# mrShark_14.net
KiCad netlist of a schematic drawn in EAGLE
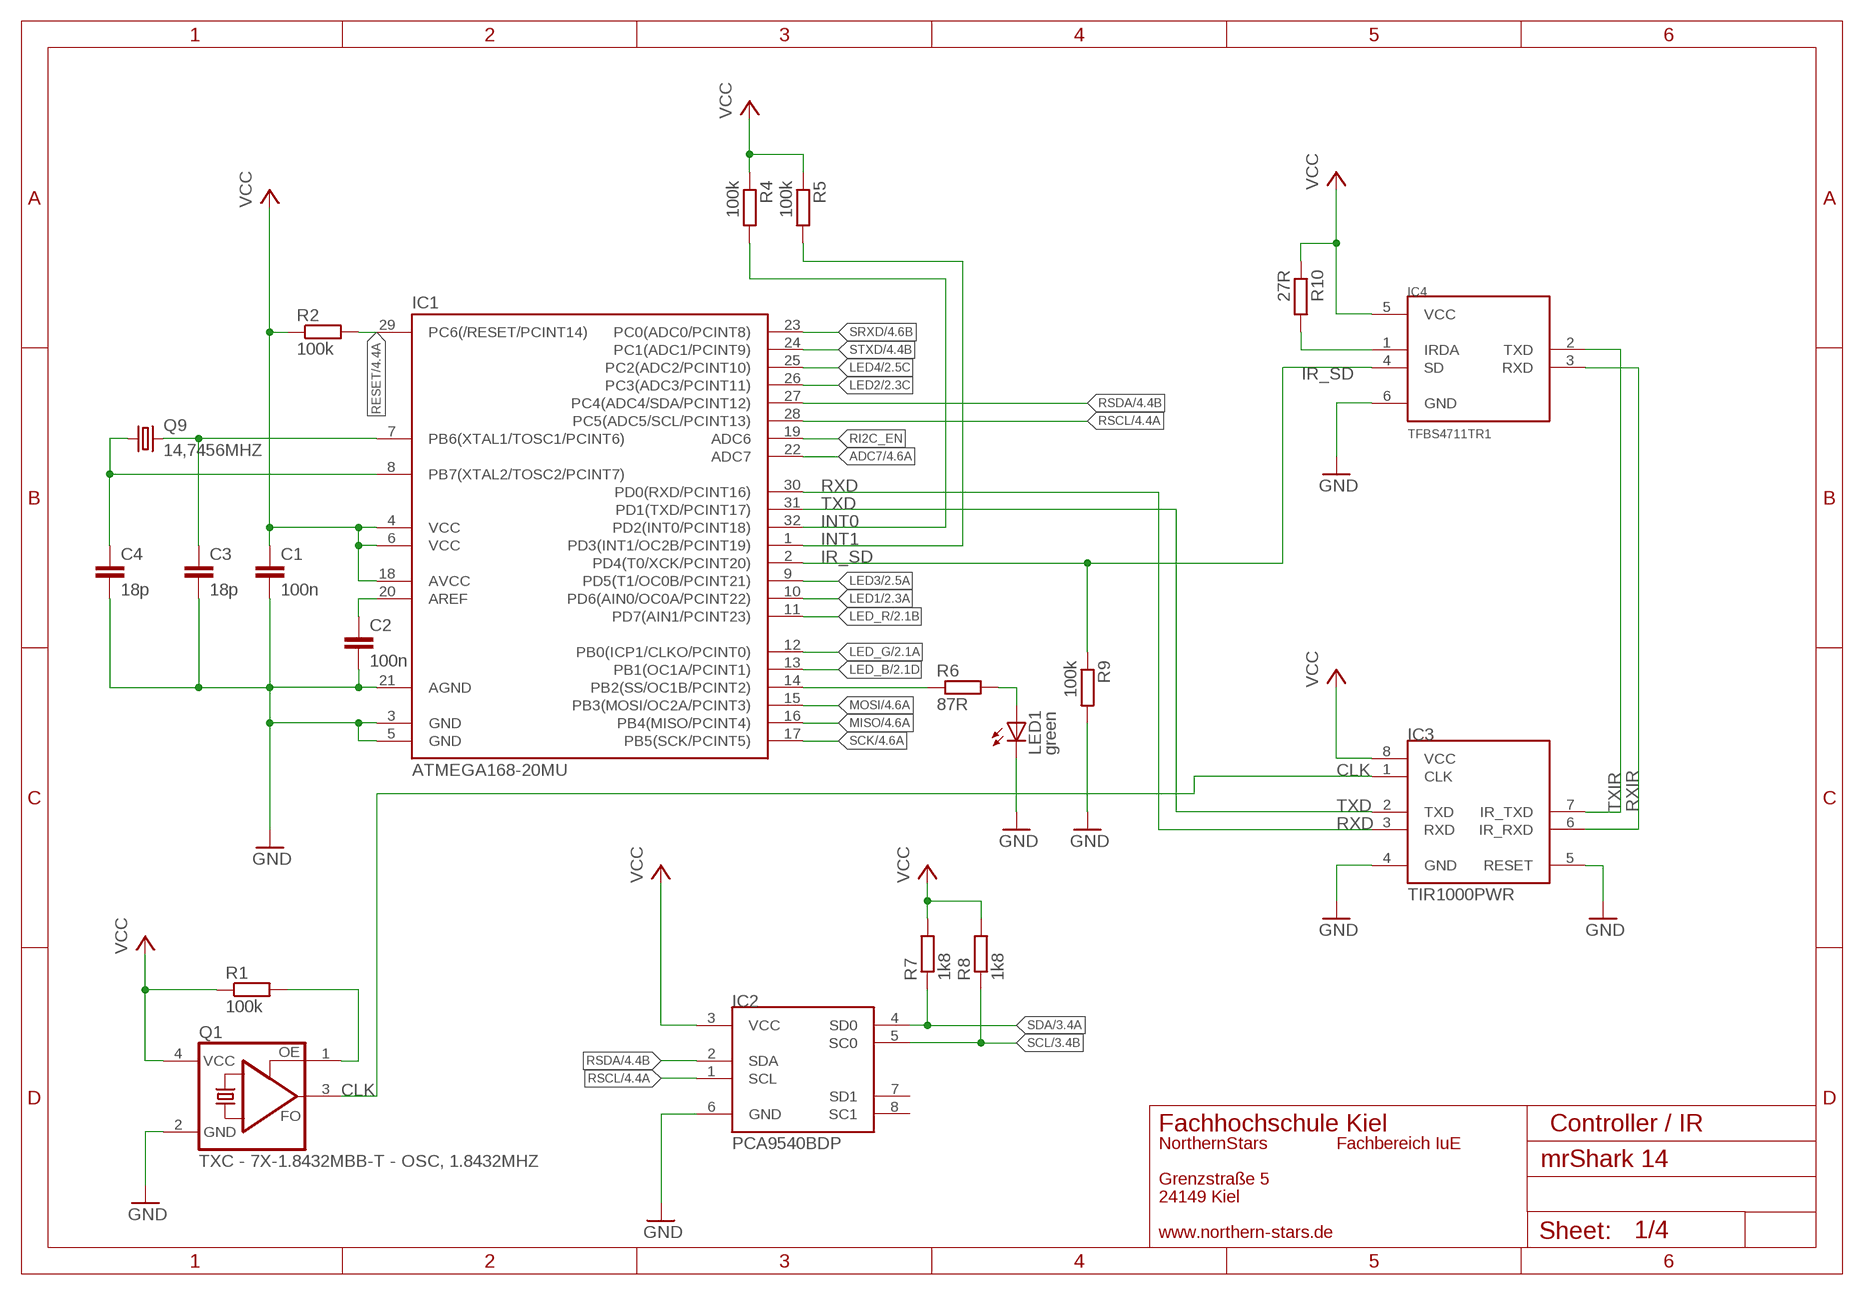
[diagram p0: schematic, sheet 1]
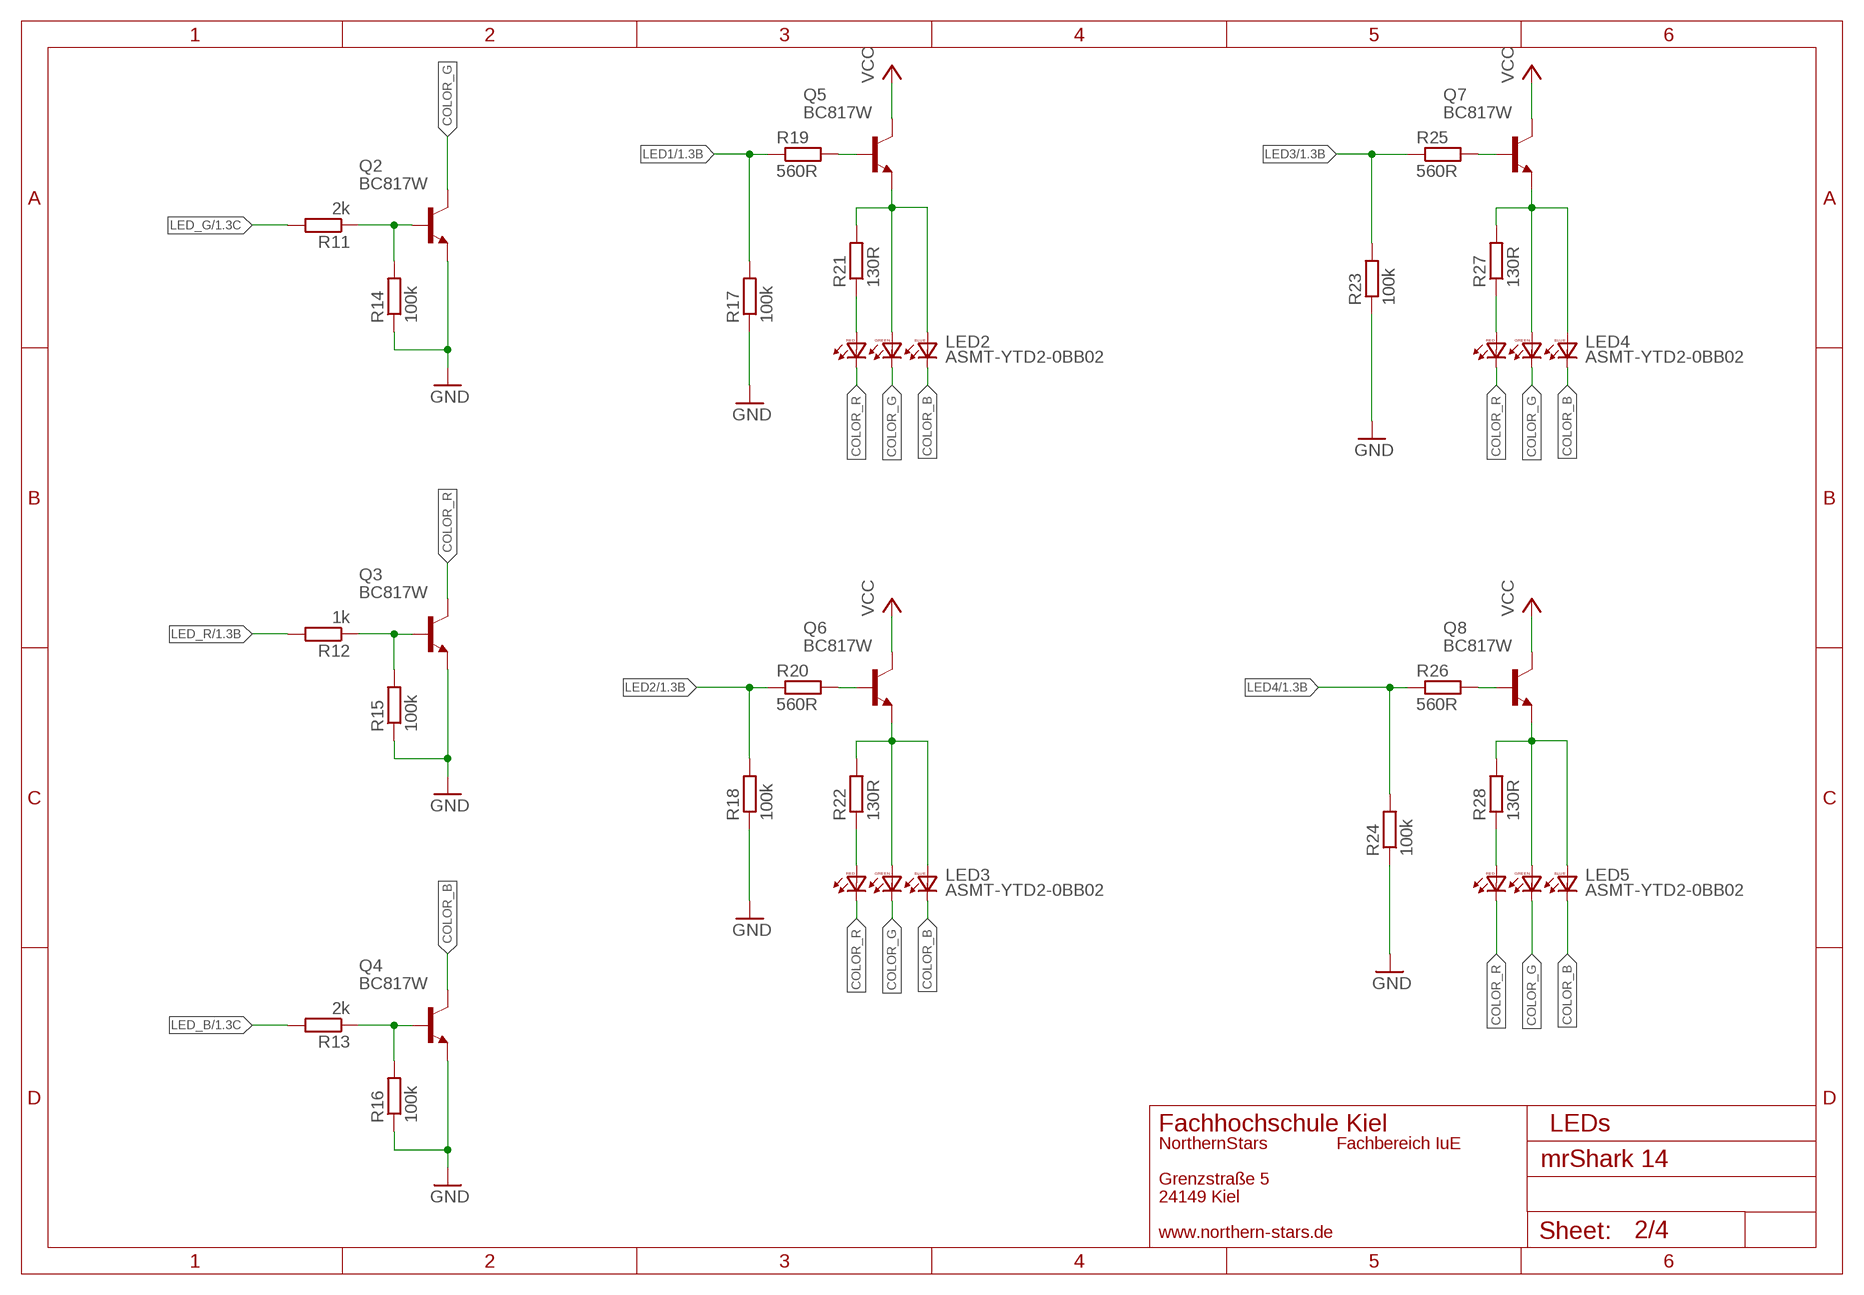
[diagram p1: schematic, sheet 2]
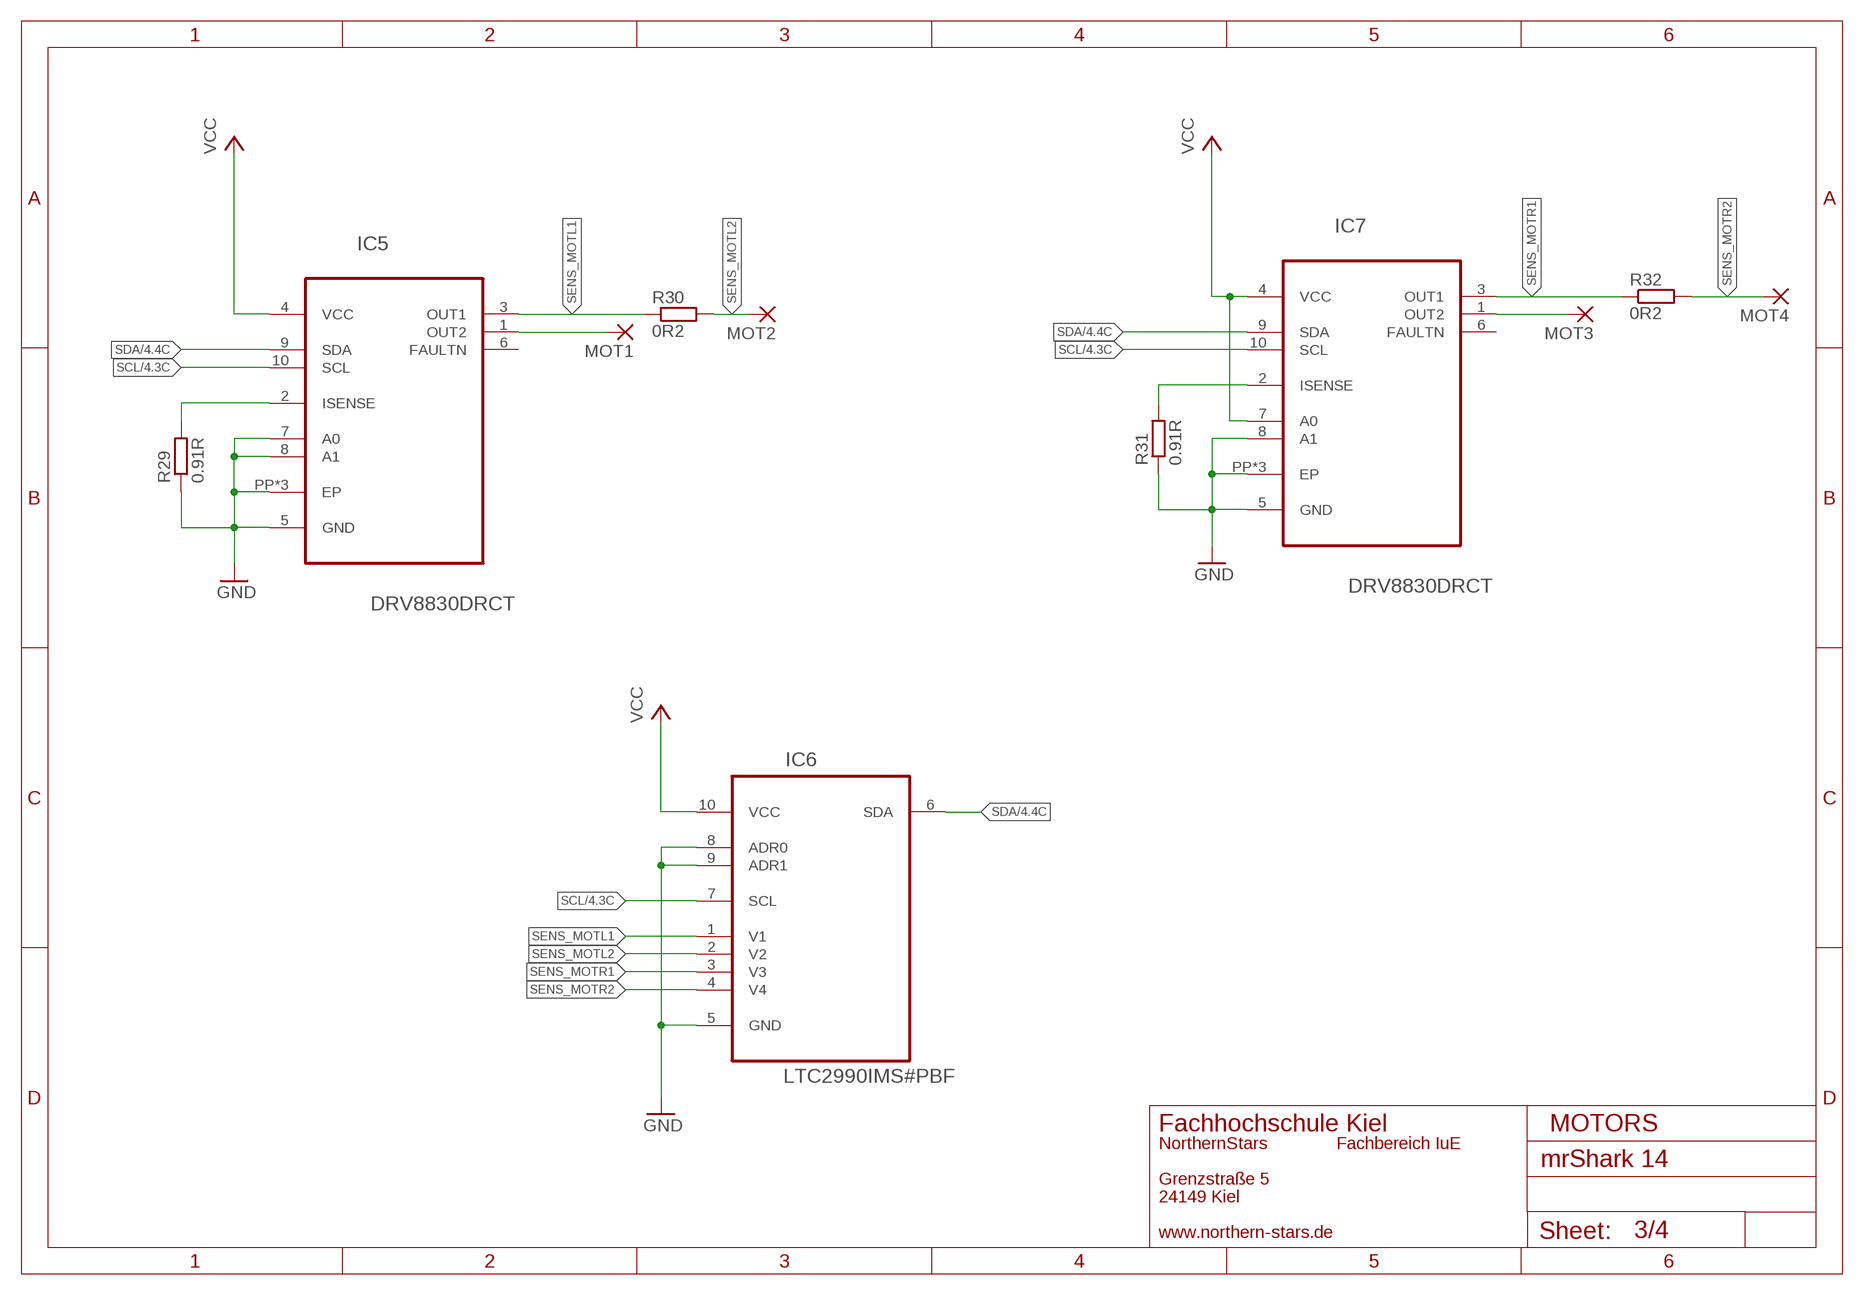
[diagram p2: schematic, sheet 3]
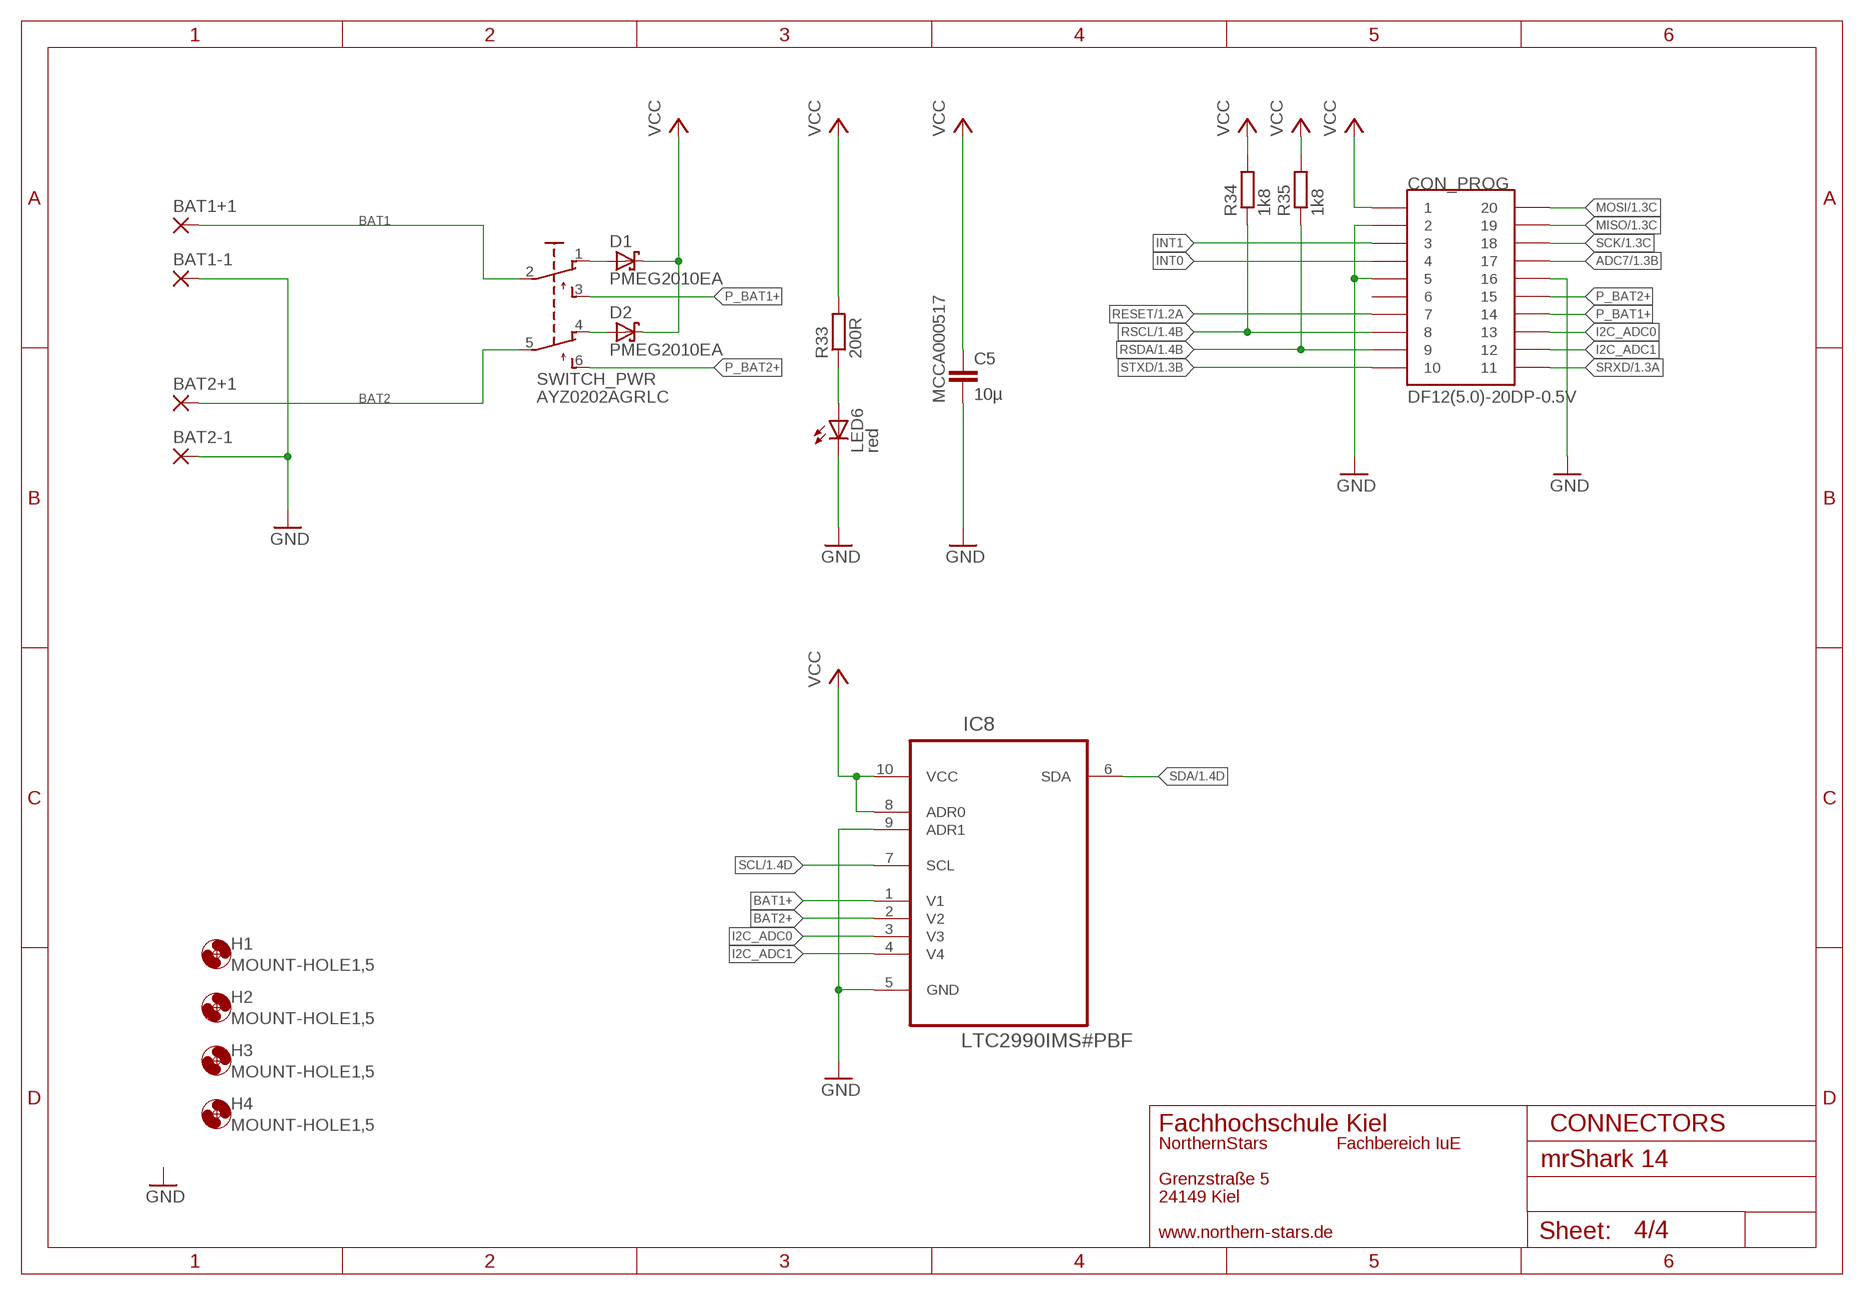
[diagram p3: schematic, sheet 4]

(export (version "E")
  (design (tool "Eeschema 10.0.6"))
  (components
    (comp (ref "BAT1+1")
      (value "1,6/0,9")
      (footprint "eagle-import:1,6_0,9")
      (libsource (lib "eagle-import") (part "1,6/0,9"))
    )
    (comp (ref "BAT1-1")
      (value "1,6/0,9")
      (footprint "eagle-import:1,6_0,9")
      (libsource (lib "eagle-import") (part "1,6/0,9"))
    )
    (comp (ref "BAT2+1")
      (value "1,6/0,9")
      (footprint "eagle-import:1,6_0,9")
      (libsource (lib "eagle-import") (part "1,6/0,9"))
    )
    (comp (ref "BAT2-1")
      (value "1,6/0,9")
      (footprint "eagle-import:1,6_0,9")
      (libsource (lib "eagle-import") (part "1,6/0,9"))
    )
    (comp (ref "C5")
      (value "10µ")
      (footprint "eagle-import:C0603K")
      (libsource (lib "eagle-import") (part "C-EUC0603K"))
    )
    (comp (ref "CON_PROG")
      (value "DF12(5.0)-20DP-0.5V")
      (footprint "eagle-import:DF12-20DP")
      (libsource (lib "eagle-import") (part "DF12-20DP"))
    )
    (comp (ref "D1")
      (value "PMEG2010EA")
      (footprint "eagle-import:SOD323-R")
      (libsource (lib "eagle-import") (part "PMEG2010EAR"))
    )
    (comp (ref "D2")
      (value "PMEG2010EA")
      (footprint "eagle-import:SOD323-R")
      (libsource (lib "eagle-import") (part "PMEG2010EAR"))
    )
    (comp (ref "H1")
      (value "MOUNT-HOLE1,5")
      (footprint "eagle-import:1,5")
      (libsource (lib "eagle-import") (part "MOUNT-HOLE1,5"))
    )
    (comp (ref "H2")
      (value "MOUNT-HOLE1,5")
      (footprint "eagle-import:1,5")
      (libsource (lib "eagle-import") (part "MOUNT-HOLE1,5"))
    )
    (comp (ref "H3")
      (value "MOUNT-HOLE1,5")
      (footprint "eagle-import:1,5")
      (libsource (lib "eagle-import") (part "MOUNT-HOLE1,5"))
    )
    (comp (ref "H4")
      (value "MOUNT-HOLE1,5")
      (footprint "eagle-import:1,5")
      (libsource (lib "eagle-import") (part "MOUNT-HOLE1,5"))
    )
    (comp (ref "IC8")
      (value "LTC2990IMS#PBF")
      (footprint "eagle-import:SOP50P490X110-10N")
      (libsource (lib "eagle-import") (part "LTC2990IMSPBF"))
    )
    (comp (ref "LED6")
      (value "red")
      (footprint "eagle-import:CHIPLED_0603")
      (libsource (lib "eagle-import") (part "LEDCHIPLED_0603"))
    )
    (comp (ref "R33")
      (value "200R")
      (footprint "eagle-import:R0201")
      (libsource (lib "eagle-import") (part "R-EU_R0201"))
    )
    (comp (ref "R34")
      (value "1k8")
      (footprint "eagle-import:R0201")
      (libsource (lib "eagle-import") (part "R-EU_R0201"))
    )
    (comp (ref "R35")
      (value "1k8")
      (footprint "eagle-import:R0201")
      (libsource (lib "eagle-import") (part "R-EU_R0201"))
    )
    (comp (ref "SWITCH_PWR")
      (value "AYZ0202AGRLC")
      (footprint "eagle-import:AYZ0202AGLRC")
      (libsource (lib "eagle-import") (part "AYZ0202AGRLC"))
    )
    (comp (ref "IC5")
      (value "DRV8830DRCT")
      (footprint "eagle-import:S-PDSO-N10")
      (libsource (lib "eagle-import") (part "DRV8830DGQRWSON"))
    )
    (comp (ref "IC6")
      (value "LTC2990IMS#PBF")
      (footprint "eagle-import:SOP50P490X110-10N")
      (libsource (lib "eagle-import") (part "LTC2990IMSPBF"))
    )
    (comp (ref "IC7")
      (value "DRV8830DRCT")
      (footprint "eagle-import:S-PDSO-N10")
      (libsource (lib "eagle-import") (part "DRV8830DGQRWSON"))
    )
    (comp (ref "MOT1")
      (value "1,6/0,9")
      (footprint "eagle-import:1,6_0,9")
      (libsource (lib "eagle-import") (part "1,6/0,9"))
    )
    (comp (ref "MOT2")
      (value "1,6/0,9")
      (footprint "eagle-import:1,6_0,9")
      (libsource (lib "eagle-import") (part "1,6/0,9"))
    )
    (comp (ref "MOT3")
      (value "1,6/0,9")
      (footprint "eagle-import:1,6_0,9")
      (libsource (lib "eagle-import") (part "1,6/0,9"))
    )
    (comp (ref "MOT4")
      (value "1,6/0,9")
      (footprint "eagle-import:1,6_0,9")
      (libsource (lib "eagle-import") (part "1,6/0,9"))
    )
    (comp (ref "R29")
      (value "0.91R")
      (footprint "eagle-import:R0603")
      (libsource (lib "eagle-import") (part "R-EU_R0603"))
    )
    (comp (ref "R30")
      (value "0R2")
      (footprint "eagle-import:R0603")
      (libsource (lib "eagle-import") (part "R-EU_R0603"))
    )
    (comp (ref "R31")
      (value "0.91R")
      (footprint "eagle-import:R0603")
      (libsource (lib "eagle-import") (part "R-EU_R0603"))
    )
    (comp (ref "R32")
      (value "0R2")
      (footprint "eagle-import:R0603")
      (libsource (lib "eagle-import") (part "R-EU_R0603"))
    )
    (comp (ref "LED2")
      (value "ASMT-YTD2-0BB02")
      (footprint "eagle-import:PLCC6K")
      (libsource (lib "eagle-import") (part "PLCC6K"))
    )
    (comp (ref "LED3")
      (value "ASMT-YTD2-0BB02")
      (footprint "eagle-import:PLCC6K")
      (libsource (lib "eagle-import") (part "PLCC6K"))
    )
    (comp (ref "LED4")
      (value "ASMT-YTD2-0BB02")
      (footprint "eagle-import:PLCC6K")
      (libsource (lib "eagle-import") (part "PLCC6K"))
    )
    (comp (ref "LED5")
      (value "ASMT-YTD2-0BB02")
      (footprint "eagle-import:PLCC6K")
      (libsource (lib "eagle-import") (part "PLCC6K"))
    )
    (comp (ref "Q2")
      (value "BC817W")
      (footprint "eagle-import:SOT323-BEC")
      (libsource (lib "eagle-import") (part "BC817W"))
    )
    (comp (ref "Q3")
      (value "BC817W")
      (footprint "eagle-import:SOT323-BEC")
      (libsource (lib "eagle-import") (part "BC817W"))
    )
    (comp (ref "Q4")
      (value "BC817W")
      (footprint "eagle-import:SOT323-BEC")
      (libsource (lib "eagle-import") (part "BC817W"))
    )
    (comp (ref "Q5")
      (value "BC817W")
      (footprint "eagle-import:SOT323-BEC")
      (libsource (lib "eagle-import") (part "BC817W"))
    )
    (comp (ref "Q6")
      (value "BC817W")
      (footprint "eagle-import:SOT323-BEC")
      (libsource (lib "eagle-import") (part "BC817W"))
    )
    (comp (ref "Q7")
      (value "BC817W")
      (footprint "eagle-import:SOT323-BEC")
      (libsource (lib "eagle-import") (part "BC817W"))
    )
    (comp (ref "Q8")
      (value "BC817W")
      (footprint "eagle-import:SOT323-BEC")
      (libsource (lib "eagle-import") (part "BC817W"))
    )
    (comp (ref "R11")
      (value "2k")
      (footprint "eagle-import:R0201")
      (libsource (lib "eagle-import") (part "R-EU_R0201"))
    )
    (comp (ref "R12")
      (value "1k")
      (footprint "eagle-import:R0201")
      (libsource (lib "eagle-import") (part "R-EU_R0201"))
    )
    (comp (ref "R13")
      (value "2k")
      (footprint "eagle-import:R0201")
      (libsource (lib "eagle-import") (part "R-EU_R0201"))
    )
    (comp (ref "R14")
      (value "100k")
      (footprint "eagle-import:R0201")
      (libsource (lib "eagle-import") (part "R-EU_R0201"))
    )
    (comp (ref "R15")
      (value "100k")
      (footprint "eagle-import:R0201")
      (libsource (lib "eagle-import") (part "R-EU_R0201"))
    )
    (comp (ref "R16")
      (value "100k")
      (footprint "eagle-import:R0201")
      (libsource (lib "eagle-import") (part "R-EU_R0201"))
    )
    (comp (ref "R17")
      (value "100k")
      (footprint "eagle-import:R0201")
      (libsource (lib "eagle-import") (part "R-EU_R0201"))
    )
    (comp (ref "R18")
      (value "100k")
      (footprint "eagle-import:R0201")
      (libsource (lib "eagle-import") (part "R-EU_R0201"))
    )
    (comp (ref "R19")
      (value "560R")
      (footprint "eagle-import:R0201")
      (libsource (lib "eagle-import") (part "R-EU_R0201"))
    )
    (comp (ref "R20")
      (value "560R")
      (footprint "eagle-import:R0201")
      (libsource (lib "eagle-import") (part "R-EU_R0201"))
    )
    (comp (ref "R21")
      (value "130R")
      (footprint "eagle-import:R0201")
      (libsource (lib "eagle-import") (part "R-EU_R0201"))
    )
    (comp (ref "R22")
      (value "130R")
      (footprint "eagle-import:R0201")
      (libsource (lib "eagle-import") (part "R-EU_R0201"))
    )
    (comp (ref "R23")
      (value "100k")
      (footprint "eagle-import:R0201")
      (libsource (lib "eagle-import") (part "R-EU_R0201"))
    )
    (comp (ref "R24")
      (value "100k")
      (footprint "eagle-import:R0201")
      (libsource (lib "eagle-import") (part "R-EU_R0201"))
    )
    (comp (ref "R25")
      (value "560R")
      (footprint "eagle-import:R0201")
      (libsource (lib "eagle-import") (part "R-EU_R0201"))
    )
    (comp (ref "R26")
      (value "560R")
      (footprint "eagle-import:R0201")
      (libsource (lib "eagle-import") (part "R-EU_R0201"))
    )
    (comp (ref "R27")
      (value "130R")
      (footprint "eagle-import:R0201")
      (libsource (lib "eagle-import") (part "R-EU_R0201"))
    )
    (comp (ref "R28")
      (value "130R")
      (footprint "eagle-import:R0201")
      (libsource (lib "eagle-import") (part "R-EU_R0201"))
    )
    (comp (ref "C1")
      (value "100n")
      (footprint "eagle-import:C0201")
      (libsource (lib "eagle-import") (part "C-EUC0201"))
    )
    (comp (ref "C2")
      (value "100n")
      (footprint "eagle-import:C0201")
      (libsource (lib "eagle-import") (part "C-EUC0201"))
    )
    (comp (ref "C3")
      (value "18p")
      (footprint "eagle-import:C0201")
      (libsource (lib "eagle-import") (part "C-EUC0201"))
    )
    (comp (ref "C4")
      (value "18p")
      (footprint "eagle-import:C0201")
      (libsource (lib "eagle-import") (part "C-EUC0201"))
    )
    (comp (ref "IC1")
      (value "ATMEGA168-20MU")
      (footprint "eagle-import:MLF32")
      (libsource (lib "eagle-import") (part "ATMEGA48/88/168-MU"))
    )
    (comp (ref "IC2")
      (value "PCA9540BDP")
      (footprint "eagle-import:TSSOP8")
      (libsource (lib "eagle-import") (part "PCA9540TSSOP8"))
    )
    (comp (ref "IC3")
      (value "TIR1000PWR")
      (footprint "eagle-import:PW_R-PDSO-G08")
      (libsource (lib "eagle-import") (part "TIR1000PWR"))
    )
    (comp (ref "IC4")
      (value "TFBS4711TR1")
      (footprint "eagle-import:TFBS4711")
      (libsource (lib "eagle-import") (part "TFBS4711TR1"))
    )
    (comp (ref "LED1")
      (value "green")
      (footprint "eagle-import:CHIPLED_0603")
      (libsource (lib "eagle-import") (part "LEDCHIPLED_0603"))
    )
    (comp (ref "Q1")
      (value "TXC - 7X-1.8432MBB-T - OSC, 1.8432MHZ")
      (footprint "eagle-import:3.2X2.5")
      (libsource (lib "eagle-import") (part "7X-SERIES"))
    )
    (comp (ref "Q9")
      (value "14,7456MHZ")
      (footprint "eagle-import:TXC_7B_SERIES")
      (libsource (lib "eagle-import") (part "TXC-7B-SERIESSMD"))
    )
    (comp (ref "R1")
      (value "100k")
      (footprint "eagle-import:R0201")
      (libsource (lib "eagle-import") (part "R-EU_R0201"))
    )
    (comp (ref "R2")
      (value "100k")
      (footprint "eagle-import:R0201")
      (libsource (lib "eagle-import") (part "R-EU_R0201"))
    )
    (comp (ref "R4")
      (value "100k")
      (footprint "eagle-import:R0201")
      (libsource (lib "eagle-import") (part "R-EU_R0201"))
    )
    (comp (ref "R5")
      (value "100k")
      (footprint "eagle-import:R0201")
      (libsource (lib "eagle-import") (part "R-EU_R0201"))
    )
    (comp (ref "R6")
      (value "87R")
      (footprint "eagle-import:R0201")
      (libsource (lib "eagle-import") (part "R-EU_R0201"))
    )
    (comp (ref "R7")
      (value "1k8")
      (footprint "eagle-import:R0201")
      (libsource (lib "eagle-import") (part "R-EU_R0201"))
    )
    (comp (ref "R8")
      (value "1k8")
      (footprint "eagle-import:R0201")
      (libsource (lib "eagle-import") (part "R-EU_R0201"))
    )
    (comp (ref "R9")
      (value "100k")
      (footprint "eagle-import:R0201")
      (libsource (lib "eagle-import") (part "R-EU_R0201"))
    )
    (comp (ref "R10")
      (value "27R")
      (footprint "eagle-import:R0201")
      (libsource (lib "eagle-import") (part "R-EU_R0201"))
    )
  )
  (nets
    (net (code "1") (name "ADC7") (class "Default")
      (node (ref "CON_PROG") (pin "17") (pinfunction "17_17") (pintype "bidirectional"))
      (node (ref "IC1") (pin "22") (pinfunction "ADC7_22") (pintype "passive"))
    )
    (net (code "2") (name "BAT1") (class "Default")
      (node (ref "BAT1+1") (pin "1") (pinfunction "P_1") (pintype "passive"))
      (node (ref "SWITCH_PWR") (pin "2") (pinfunction "P_2") (pintype "passive"))
    )
    (net (code "3") (name "BAT1+") (class "Default")
      (node (ref "D1") (pin "A") (pinfunction "A_A") (pintype "passive"))
      (node (ref "IC8") (pin "1") (pinfunction "V1_1") (pintype "input"))
      (node (ref "SWITCH_PWR") (pin "1") (pinfunction "O_1") (pintype "passive"))
    )
    (net (code "4") (name "BAT2") (class "Default")
      (node (ref "BAT2+1") (pin "1") (pinfunction "P_1") (pintype "passive"))
      (node (ref "SWITCH_PWR") (pin "5") (pinfunction "P1_5") (pintype "passive"))
    )
    (net (code "5") (name "BAT2+") (class "Default")
      (node (ref "D2") (pin "A") (pinfunction "A_A") (pintype "passive"))
      (node (ref "IC8") (pin "2") (pinfunction "V2_2") (pintype "input"))
      (node (ref "SWITCH_PWR") (pin "4") (pinfunction "O1_4") (pintype "passive"))
    )
    (net (code "6") (name "CLK") (class "Default")
      (node (ref "IC3") (pin "1") (pinfunction "CLK_1") (pintype "bidirectional"))
      (node (ref "Q1") (pin "3") (pinfunction "FO_3") (pintype "output"))
    )
    (net (code "7") (name "COLOR_B") (class "Default")
      (node (ref "LED2") (pin "1") (pinfunction "BC_1") (pintype "passive"))
      (node (ref "LED3") (pin "1") (pinfunction "BC_1") (pintype "passive"))
      (node (ref "LED4") (pin "1") (pinfunction "BC_1") (pintype "passive"))
      (node (ref "LED5") (pin "1") (pinfunction "BC_1") (pintype "passive"))
      (node (ref "Q4") (pin "C") (pinfunction "C_C") (pintype "passive"))
    )
    (net (code "8") (name "COLOR_G") (class "Default")
      (node (ref "LED2") (pin "2") (pinfunction "GC_2") (pintype "passive"))
      (node (ref "LED3") (pin "2") (pinfunction "GC_2") (pintype "passive"))
      (node (ref "LED4") (pin "2") (pinfunction "GC_2") (pintype "passive"))
      (node (ref "LED5") (pin "2") (pinfunction "GC_2") (pintype "passive"))
      (node (ref "Q2") (pin "C") (pinfunction "C_C") (pintype "passive"))
    )
    (net (code "9") (name "COLOR_R") (class "Default")
      (node (ref "LED2") (pin "3") (pinfunction "RC_3") (pintype "passive"))
      (node (ref "LED3") (pin "3") (pinfunction "RC_3") (pintype "passive"))
      (node (ref "LED4") (pin "3") (pinfunction "RC_3") (pintype "passive"))
      (node (ref "LED5") (pin "3") (pinfunction "RC_3") (pintype "passive"))
      (node (ref "Q3") (pin "C") (pinfunction "C_C") (pintype "passive"))
    )
    (net (code "10") (name "GND") (class "Default")
      (node (ref "BAT1-1") (pin "1") (pinfunction "P_1") (pintype "passive"))
      (node (ref "BAT2-1") (pin "1") (pinfunction "P_1") (pintype "passive"))
      (node (ref "C1") (pin "2") (pinfunction "2_2") (pintype "passive"))
      (node (ref "C2") (pin "2") (pinfunction "2_2") (pintype "passive"))
      (node (ref "C3") (pin "2") (pinfunction "2_2") (pintype "passive"))
      (node (ref "C4") (pin "2") (pinfunction "2_2") (pintype "passive"))
      (node (ref "C5") (pin "2") (pinfunction "2_2") (pintype "passive"))
      (node (ref "CON_PROG") (pin "16") (pinfunction "16_16") (pintype "bidirectional"))
      (node (ref "CON_PROG") (pin "2") (pinfunction "2_2") (pintype "bidirectional"))
      (node (ref "CON_PROG") (pin "5") (pinfunction "5_5") (pintype "bidirectional"))
      (node (ref "IC1") (pin "21") (pinfunction "AGND_21") (pintype "power_in"))
      (node (ref "IC1") (pin "3") (pinfunction "GND_3") (pintype "power_in"))
      (node (ref "IC1") (pin "5") (pinfunction "GND_5") (pintype "power_in"))
      (node (ref "IC2") (pin "6") (pinfunction "GND_6") (pintype "bidirectional"))
      (node (ref "IC3") (pin "4") (pinfunction "GND_4") (pintype "bidirectional"))
      (node (ref "IC3") (pin "5") (pinfunction "RESET_5") (pintype "bidirectional"))
      (node (ref "IC4") (pin "6") (pinfunction "GND_6") (pintype "bidirectional"))
      (node (ref "IC5") (pin "5") (pinfunction "GND_5") (pintype "passive"))
      (node (ref "IC5") (pin "7") (pinfunction "A0_7") (pintype "input"))
      (node (ref "IC5") (pin "8") (pinfunction "A1_8") (pintype "input"))
      (node (ref "IC5") (pin "PP") (pinfunction "EP_PP") (pintype "passive"))
      (node (ref "IC5") (pin "PP@1") (pinfunction "EP_PP@1") (pintype "passive"))
      (node (ref "IC5") (pin "PP@2") (pinfunction "EP_PP@2") (pintype "passive"))
      (node (ref "IC6") (pin "5") (pinfunction "GND_5") (pintype "passive"))
      (node (ref "IC6") (pin "8") (pinfunction "ADR0_8") (pintype "input"))
      (node (ref "IC6") (pin "9") (pinfunction "ADR1_9") (pintype "input"))
      (node (ref "IC7") (pin "5") (pinfunction "GND_5") (pintype "passive"))
      (node (ref "IC7") (pin "8") (pinfunction "A1_8") (pintype "input"))
      (node (ref "IC7") (pin "PP") (pinfunction "EP_PP") (pintype "passive"))
      (node (ref "IC7") (pin "PP@1") (pinfunction "EP_PP@1") (pintype "passive"))
      (node (ref "IC7") (pin "PP@2") (pinfunction "EP_PP@2") (pintype "passive"))
      (node (ref "IC8") (pin "5") (pinfunction "GND_5") (pintype "passive"))
      (node (ref "IC8") (pin "9") (pinfunction "ADR1_9") (pintype "input"))
      (node (ref "LED1") (pin "C") (pinfunction "C_C") (pintype "passive"))
      (node (ref "LED6") (pin "C") (pinfunction "C_C") (pintype "passive"))
      (node (ref "Q1") (pin "2") (pinfunction "GND_2") (pintype "power_in"))
      (node (ref "Q2") (pin "E") (pinfunction "E_E") (pintype "passive"))
      (node (ref "Q3") (pin "E") (pinfunction "E_E") (pintype "passive"))
      (node (ref "Q4") (pin "E") (pinfunction "E_E") (pintype "passive"))
      (node (ref "R14") (pin "1") (pinfunction "1_1") (pintype "passive"))
      (node (ref "R15") (pin "1") (pinfunction "1_1") (pintype "passive"))
      (node (ref "R16") (pin "1") (pinfunction "1_1") (pintype "passive"))
      (node (ref "R17") (pin "1") (pinfunction "1_1") (pintype "passive"))
      (node (ref "R18") (pin "1") (pinfunction "1_1") (pintype "passive"))
      (node (ref "R23") (pin "1") (pinfunction "1_1") (pintype "passive"))
      (node (ref "R24") (pin "1") (pinfunction "1_1") (pintype "passive"))
      (node (ref "R29") (pin "1") (pinfunction "1_1") (pintype "passive"))
      (node (ref "R31") (pin "1") (pinfunction "1_1") (pintype "passive"))
      (node (ref "R9") (pin "2") (pinfunction "2_2") (pintype "passive"))
    )
    (net (code "11") (name "I2C_ADC0") (class "Default")
      (node (ref "CON_PROG") (pin "13") (pinfunction "13_13") (pintype "bidirectional"))
      (node (ref "IC8") (pin "3") (pinfunction "V3_3") (pintype "input"))
    )
    (net (code "12") (name "I2C_ADC1") (class "Default")
      (node (ref "CON_PROG") (pin "12") (pinfunction "12_12") (pintype "bidirectional"))
      (node (ref "IC8") (pin "4") (pinfunction "V4_4") (pintype "input"))
    )
    (net (code "13") (name "INT0") (class "Default")
      (node (ref "CON_PROG") (pin "4") (pinfunction "4_4") (pintype "bidirectional"))
      (node (ref "IC1") (pin "32") (pinfunction "PD2(INT0/PCINT18)_32") (pintype "bidirectional"))
      (node (ref "R4") (pin "2") (pinfunction "2_2") (pintype "passive"))
    )
    (net (code "14") (name "INT1") (class "Default")
      (node (ref "CON_PROG") (pin "3") (pinfunction "3_3") (pintype "bidirectional"))
      (node (ref "IC1") (pin "1") (pinfunction "PD3(INT1/OC2B/PCINT19)_1") (pintype "bidirectional"))
      (node (ref "R5") (pin "2") (pinfunction "2_2") (pintype "passive"))
    )
    (net (code "15") (name "IR_SD") (class "Default")
      (node (ref "IC1") (pin "2") (pinfunction "PD4(T0/XCK/PCINT20)_2") (pintype "bidirectional"))
      (node (ref "IC4") (pin "4") (pinfunction "SD_4") (pintype "bidirectional"))
      (node (ref "R9") (pin "1") (pinfunction "1_1") (pintype "passive"))
    )
    (net (code "16") (name "LED1") (class "Default")
      (node (ref "IC1") (pin "10") (pinfunction "PD6(AIN0/OC0A/PCINT22)_10") (pintype "bidirectional"))
      (node (ref "R17") (pin "2") (pinfunction "2_2") (pintype "passive"))
      (node (ref "R19") (pin "1") (pinfunction "1_1") (pintype "passive"))
    )
    (net (code "17") (name "LED2") (class "Default")
      (node (ref "IC1") (pin "26") (pinfunction "PC3(ADC3/PCINT11)_26") (pintype "bidirectional"))
      (node (ref "R18") (pin "2") (pinfunction "2_2") (pintype "passive"))
      (node (ref "R20") (pin "1") (pinfunction "1_1") (pintype "passive"))
    )
    (net (code "18") (name "LED3") (class "Default")
      (node (ref "IC1") (pin "9") (pinfunction "PD5(T1/OC0B/PCINT21)_9") (pintype "bidirectional"))
      (node (ref "R23") (pin "2") (pinfunction "2_2") (pintype "passive"))
      (node (ref "R25") (pin "1") (pinfunction "1_1") (pintype "passive"))
    )
    (net (code "19") (name "LED4") (class "Default")
      (node (ref "IC1") (pin "25") (pinfunction "PC2(ADC2/PCINT10)_25") (pintype "bidirectional"))
      (node (ref "R24") (pin "2") (pinfunction "2_2") (pintype "passive"))
      (node (ref "R26") (pin "1") (pinfunction "1_1") (pintype "passive"))
    )
    (net (code "20") (name "LED_B") (class "Default")
      (node (ref "IC1") (pin "13") (pinfunction "PB1(OC1A/PCINT1)_13") (pintype "bidirectional"))
      (node (ref "R13") (pin "2") (pinfunction "2_2") (pintype "passive"))
    )
    (net (code "21") (name "LED_G") (class "Default")
      (node (ref "IC1") (pin "12") (pinfunction "PB0(ICP1/CLKO/PCINT0)_12") (pintype "bidirectional"))
      (node (ref "R11") (pin "2") (pinfunction "2_2") (pintype "passive"))
    )
    (net (code "22") (name "LED_R") (class "Default")
      (node (ref "IC1") (pin "11") (pinfunction "PD7(AIN1/PCINT23)_11") (pintype "bidirectional"))
      (node (ref "R12") (pin "2") (pinfunction "2_2") (pintype "passive"))
    )
    (net (code "23") (name "MISO") (class "Default")
      (node (ref "CON_PROG") (pin "19") (pinfunction "19_19") (pintype "bidirectional"))
      (node (ref "IC1") (pin "16") (pinfunction "PB4(MISO/PCINT4)_16") (pintype "bidirectional"))
    )
    (net (code "24") (name "MOSI") (class "Default")
      (node (ref "CON_PROG") (pin "20") (pinfunction "20_20") (pintype "bidirectional"))
      (node (ref "IC1") (pin "15") (pinfunction "PB3(MOSI/OC2A/PCINT3)_15") (pintype "bidirectional"))
    )
    (net (code "25") (name "Net-(IC1-AREF)") (class "Default")
      (node (ref "C2") (pin "1") (pinfunction "1_1") (pintype "passive"))
      (node (ref "IC1") (pin "20") (pinfunction "AREF_20") (pintype "passive"))
    )
    (net (code "26") (name "Net-(IC1-PB2(SS{slash}OC1B{slash}PCINT2))") (class "Default")
      (node (ref "IC1") (pin "14") (pinfunction "PB2(SS/OC1B/PCINT2)_14") (pintype "bidirectional"))
      (node (ref "R6") (pin "1") (pinfunction "1_1") (pintype "passive"))
    )
    (net (code "27") (name "Net-(IC1-PB6(XTAL1{slash}TOSC1{slash}PCINT6))") (class "Default")
      (node (ref "C3") (pin "1") (pinfunction "1_1") (pintype "passive"))
      (node (ref "IC1") (pin "7") (pinfunction "PB6(XTAL1/TOSC1/PCINT6)_7") (pintype "bidirectional"))
      (node (ref "Q9") (pin "3") (pinfunction "2_3") (pintype "passive"))
    )
    (net (code "28") (name "Net-(IC1-PB7(XTAL2{slash}TOSC2{slash}PCINT7))") (class "Default")
      (node (ref "C4") (pin "1") (pinfunction "1_1") (pintype "passive"))
      (node (ref "IC1") (pin "8") (pinfunction "PB7(XTAL2/TOSC2/PCINT7)_8") (pintype "bidirectional"))
      (node (ref "Q9") (pin "1") (pinfunction "1_1") (pintype "passive"))
    )
    (net (code "29") (name "Net-(IC4-IRDA)") (class "Default")
      (node (ref "IC4") (pin "1") (pinfunction "IRDA_1") (pintype "bidirectional"))
      (node (ref "R10") (pin "2") (pinfunction "2_2") (pintype "passive"))
    )
    (net (code "30") (name "Net-(IC5-ISENSE)") (class "Default")
      (node (ref "IC5") (pin "2") (pinfunction "ISENSE_2") (pintype "input"))
      (node (ref "R29") (pin "2") (pinfunction "2_2") (pintype "passive"))
    )
    (net (code "31") (name "Net-(IC5-OUT2)") (class "Default")
      (node (ref "IC5") (pin "1") (pinfunction "OUT2_1") (pintype "output"))
      (node (ref "MOT1") (pin "1") (pinfunction "P_1") (pintype "passive"))
    )
    (net (code "32") (name "Net-(IC7-ISENSE)") (class "Default")
      (node (ref "IC7") (pin "2") (pinfunction "ISENSE_2") (pintype "input"))
      (node (ref "R31") (pin "2") (pinfunction "2_2") (pintype "passive"))
    )
    (net (code "33") (name "Net-(IC7-OUT2)") (class "Default")
      (node (ref "IC7") (pin "1") (pinfunction "OUT2_1") (pintype "output"))
      (node (ref "MOT3") (pin "1") (pinfunction "P_1") (pintype "passive"))
    )
    (net (code "34") (name "Net-(LED1-PadA)") (class "Default")
      (node (ref "LED1") (pin "A") (pinfunction "A_A") (pintype "passive"))
      (node (ref "R6") (pin "2") (pinfunction "2_2") (pintype "passive"))
    )
    (net (code "35") (name "Net-(LED2-BA)") (class "Default")
      (node (ref "LED2") (pin "5") (pinfunction "GA_5") (pintype "passive"))
      (node (ref "LED2") (pin "6") (pinfunction "BA_6") (pintype "passive"))
      (node (ref "Q5") (pin "E") (pinfunction "E_E") (pintype "passive"))
      (node (ref "R21") (pin "2") (pinfunction "2_2") (pintype "passive"))
    )
    (net (code "36") (name "Net-(LED2-RA)") (class "Default")
      (node (ref "LED2") (pin "4") (pinfunction "RA_4") (pintype "passive"))
      (node (ref "R21") (pin "1") (pinfunction "1_1") (pintype "passive"))
    )
    (net (code "37") (name "Net-(LED3-BA)") (class "Default")
      (node (ref "LED3") (pin "5") (pinfunction "GA_5") (pintype "passive"))
      (node (ref "LED3") (pin "6") (pinfunction "BA_6") (pintype "passive"))
      (node (ref "Q6") (pin "E") (pinfunction "E_E") (pintype "passive"))
      (node (ref "R22") (pin "2") (pinfunction "2_2") (pintype "passive"))
    )
    (net (code "38") (name "Net-(LED3-RA)") (class "Default")
      (node (ref "LED3") (pin "4") (pinfunction "RA_4") (pintype "passive"))
      (node (ref "R22") (pin "1") (pinfunction "1_1") (pintype "passive"))
    )
    (net (code "39") (name "Net-(LED4-BA)") (class "Default")
      (node (ref "LED4") (pin "5") (pinfunction "GA_5") (pintype "passive"))
      (node (ref "LED4") (pin "6") (pinfunction "BA_6") (pintype "passive"))
      (node (ref "Q7") (pin "E") (pinfunction "E_E") (pintype "passive"))
      (node (ref "R27") (pin "2") (pinfunction "2_2") (pintype "passive"))
    )
    (net (code "40") (name "Net-(LED4-RA)") (class "Default")
      (node (ref "LED4") (pin "4") (pinfunction "RA_4") (pintype "passive"))
      (node (ref "R27") (pin "1") (pinfunction "1_1") (pintype "passive"))
    )
    (net (code "41") (name "Net-(LED5-BA)") (class "Default")
      (node (ref "LED5") (pin "5") (pinfunction "GA_5") (pintype "passive"))
      (node (ref "LED5") (pin "6") (pinfunction "BA_6") (pintype "passive"))
      (node (ref "Q8") (pin "E") (pinfunction "E_E") (pintype "passive"))
      (node (ref "R28") (pin "2") (pinfunction "2_2") (pintype "passive"))
    )
    (net (code "42") (name "Net-(LED5-RA)") (class "Default")
      (node (ref "LED5") (pin "4") (pinfunction "RA_4") (pintype "passive"))
      (node (ref "R28") (pin "1") (pinfunction "1_1") (pintype "passive"))
    )
    (net (code "43") (name "Net-(LED6-PadA)") (class "Default")
      (node (ref "LED6") (pin "A") (pinfunction "A_A") (pintype "passive"))
      (node (ref "R33") (pin "1") (pinfunction "1_1") (pintype "passive"))
    )
    (net (code "44") (name "Net-(Q1-OE)") (class "Default")
      (node (ref "Q1") (pin "1") (pinfunction "OE_1") (pintype "input"))
      (node (ref "R1") (pin "2") (pinfunction "2_2") (pintype "passive"))
    )
    (net (code "45") (name "Net-(Q2-PadB)") (class "Default")
      (node (ref "Q2") (pin "B") (pinfunction "B_B") (pintype "passive"))
      (node (ref "R11") (pin "1") (pinfunction "1_1") (pintype "passive"))
      (node (ref "R14") (pin "2") (pinfunction "2_2") (pintype "passive"))
    )
    (net (code "46") (name "Net-(Q3-PadB)") (class "Default")
      (node (ref "Q3") (pin "B") (pinfunction "B_B") (pintype "passive"))
      (node (ref "R12") (pin "1") (pinfunction "1_1") (pintype "passive"))
      (node (ref "R15") (pin "2") (pinfunction "2_2") (pintype "passive"))
    )
    (net (code "47") (name "Net-(Q4-PadB)") (class "Default")
      (node (ref "Q4") (pin "B") (pinfunction "B_B") (pintype "passive"))
      (node (ref "R13") (pin "1") (pinfunction "1_1") (pintype "passive"))
      (node (ref "R16") (pin "2") (pinfunction "2_2") (pintype "passive"))
    )
    (net (code "48") (name "Net-(Q5-PadB)") (class "Default")
      (node (ref "Q5") (pin "B") (pinfunction "B_B") (pintype "passive"))
      (node (ref "R19") (pin "2") (pinfunction "2_2") (pintype "passive"))
    )
    (net (code "49") (name "Net-(Q6-PadB)") (class "Default")
      (node (ref "Q6") (pin "B") (pinfunction "B_B") (pintype "passive"))
      (node (ref "R20") (pin "2") (pinfunction "2_2") (pintype "passive"))
    )
    (net (code "50") (name "Net-(Q7-PadB)") (class "Default")
      (node (ref "Q7") (pin "B") (pinfunction "B_B") (pintype "passive"))
      (node (ref "R25") (pin "2") (pinfunction "2_2") (pintype "passive"))
    )
    (net (code "51") (name "Net-(Q8-PadB)") (class "Default")
      (node (ref "Q8") (pin "B") (pinfunction "B_B") (pintype "passive"))
      (node (ref "R26") (pin "2") (pinfunction "2_2") (pintype "passive"))
    )
    (net (code "52") (name "P_BAT1+") (class "Default")
      (node (ref "CON_PROG") (pin "14") (pinfunction "14_14") (pintype "bidirectional"))
      (node (ref "SWITCH_PWR") (pin "3") (pinfunction "S_3") (pintype "passive"))
    )
    (net (code "53") (name "P_BAT2+") (class "Default")
      (node (ref "CON_PROG") (pin "15") (pinfunction "15_15") (pintype "bidirectional"))
      (node (ref "SWITCH_PWR") (pin "6") (pinfunction "S1_6") (pintype "passive"))
    )
    (net (code "54") (name "RESET") (class "Default")
      (node (ref "CON_PROG") (pin "7") (pinfunction "7_7") (pintype "bidirectional"))
      (node (ref "IC1") (pin "29") (pinfunction "PC6(/RESET/PCINT14)_29") (pintype "bidirectional"))
      (node (ref "R2") (pin "2") (pinfunction "2_2") (pintype "passive"))
    )
    (net (code "55") (name "RI2C_EN") (class "Default")
      (node (ref "IC1") (pin "19") (pinfunction "ADC6_19") (pintype "passive"))
    )
    (net (code "56") (name "RSCL") (class "Default")
      (node (ref "CON_PROG") (pin "8") (pinfunction "8_8") (pintype "bidirectional"))
      (node (ref "IC1") (pin "28") (pinfunction "PC5(ADC5/SCL/PCINT13)_28") (pintype "bidirectional"))
      (node (ref "IC2") (pin "1") (pinfunction "SCL_1") (pintype "bidirectional"))
      (node (ref "R34") (pin "1") (pinfunction "1_1") (pintype "passive"))
    )
    (net (code "57") (name "RSDA") (class "Default")
      (node (ref "CON_PROG") (pin "9") (pinfunction "9_9") (pintype "bidirectional"))
      (node (ref "IC1") (pin "27") (pinfunction "PC4(ADC4/SDA/PCINT12)_27") (pintype "bidirectional"))
      (node (ref "IC2") (pin "2") (pinfunction "SDA_2") (pintype "bidirectional"))
      (node (ref "R35") (pin "1") (pinfunction "1_1") (pintype "passive"))
    )
    (net (code "58") (name "RXD") (class "Default")
      (node (ref "IC1") (pin "30") (pinfunction "PD0(RXD/PCINT16)_30") (pintype "bidirectional"))
      (node (ref "IC3") (pin "3") (pinfunction "RXD_3") (pintype "bidirectional"))
    )
    (net (code "59") (name "RXIR") (class "Default")
      (node (ref "IC3") (pin "6") (pinfunction "IR_RXD_6") (pintype "bidirectional"))
      (node (ref "IC4") (pin "3") (pinfunction "RXD_3") (pintype "output"))
    )
    (net (code "60") (name "SCK") (class "Default")
      (node (ref "CON_PROG") (pin "18") (pinfunction "18_18") (pintype "bidirectional"))
      (node (ref "IC1") (pin "17") (pinfunction "PB5(SCK/PCINT5)_17") (pintype "bidirectional"))
    )
    (net (code "61") (name "SCL") (class "Default")
      (node (ref "IC2") (pin "5") (pinfunction "SC0_5") (pintype "bidirectional"))
      (node (ref "IC5") (pin "10") (pinfunction "SCL_10") (pintype "input"))
      (node (ref "IC6") (pin "7") (pinfunction "SCL_7") (pintype "input"))
      (node (ref "IC7") (pin "10") (pinfunction "SCL_10") (pintype "input"))
      (node (ref "IC8") (pin "7") (pinfunction "SCL_7") (pintype "input"))
      (node (ref "R8") (pin "1") (pinfunction "1_1") (pintype "passive"))
    )
    (net (code "62") (name "SDA") (class "Default")
      (node (ref "IC2") (pin "4") (pinfunction "SD0_4") (pintype "bidirectional"))
      (node (ref "IC5") (pin "9") (pinfunction "SDA_9") (pintype "bidirectional"))
      (node (ref "IC6") (pin "6") (pinfunction "SDA_6") (pintype "bidirectional"))
      (node (ref "IC7") (pin "9") (pinfunction "SDA_9") (pintype "bidirectional"))
      (node (ref "IC8") (pin "6") (pinfunction "SDA_6") (pintype "bidirectional"))
      (node (ref "R7") (pin "1") (pinfunction "1_1") (pintype "passive"))
    )
    (net (code "63") (name "SENS_MOTL1") (class "Default")
      (node (ref "IC5") (pin "3") (pinfunction "OUT1_3") (pintype "output"))
      (node (ref "IC6") (pin "1") (pinfunction "V1_1") (pintype "input"))
      (node (ref "R30") (pin "1") (pinfunction "1_1") (pintype "passive"))
    )
    (net (code "64") (name "SENS_MOTL2") (class "Default")
      (node (ref "IC6") (pin "2") (pinfunction "V2_2") (pintype "input"))
      (node (ref "MOT2") (pin "1") (pinfunction "P_1") (pintype "passive"))
      (node (ref "R30") (pin "2") (pinfunction "2_2") (pintype "passive"))
    )
    (net (code "65") (name "SENS_MOTR1") (class "Default")
      (node (ref "IC6") (pin "3") (pinfunction "V3_3") (pintype "input"))
      (node (ref "IC7") (pin "3") (pinfunction "OUT1_3") (pintype "output"))
      (node (ref "R32") (pin "1") (pinfunction "1_1") (pintype "passive"))
    )
    (net (code "66") (name "SENS_MOTR2") (class "Default")
      (node (ref "IC6") (pin "4") (pinfunction "V4_4") (pintype "input"))
      (node (ref "MOT4") (pin "1") (pinfunction "P_1") (pintype "passive"))
      (node (ref "R32") (pin "2") (pinfunction "2_2") (pintype "passive"))
    )
    (net (code "67") (name "SRXD") (class "Default")
      (node (ref "CON_PROG") (pin "11") (pinfunction "11_11") (pintype "bidirectional"))
      (node (ref "IC1") (pin "23") (pinfunction "PC0(ADC0/PCINT8)_23") (pintype "bidirectional"))
    )
    (net (code "68") (name "STXD") (class "Default")
      (node (ref "CON_PROG") (pin "10") (pinfunction "10_10") (pintype "bidirectional"))
      (node (ref "IC1") (pin "24") (pinfunction "PC1(ADC1/PCINT9)_24") (pintype "bidirectional"))
    )
    (net (code "69") (name "TXD") (class "Default")
      (node (ref "IC1") (pin "31") (pinfunction "PD1(TXD/PCINT17)_31") (pintype "bidirectional"))
      (node (ref "IC3") (pin "2") (pinfunction "TXD_2") (pintype "bidirectional"))
    )
    (net (code "70") (name "TXIR") (class "Default")
      (node (ref "IC3") (pin "7") (pinfunction "IR_TXD_7") (pintype "bidirectional"))
      (node (ref "IC4") (pin "2") (pinfunction "TXD_2") (pintype "input"))
    )
    (net (code "71") (name "VCC") (class "Default")
      (node (ref "C1") (pin "1") (pinfunction "1_1") (pintype "passive"))
      (node (ref "C5") (pin "1") (pinfunction "1_1") (pintype "passive"))
      (node (ref "CON_PROG") (pin "1") (pinfunction "1_1") (pintype "bidirectional"))
      (node (ref "D1") (pin "C") (pinfunction "C_C") (pintype "passive"))
      (node (ref "D2") (pin "C") (pinfunction "C_C") (pintype "passive"))
      (node (ref "IC1") (pin "18") (pinfunction "AVCC_18") (pintype "passive"))
      (node (ref "IC1") (pin "4") (pinfunction "VCC_4") (pintype "power_in"))
      (node (ref "IC1") (pin "6") (pinfunction "VCC_6") (pintype "power_in"))
      (node (ref "IC2") (pin "3") (pinfunction "VCC_3") (pintype "bidirectional"))
      (node (ref "IC3") (pin "8") (pinfunction "VCC_8") (pintype "bidirectional"))
      (node (ref "IC4") (pin "5") (pinfunction "VCC_5") (pintype "power_in"))
      (node (ref "IC5") (pin "4") (pinfunction "VCC_4") (pintype "power_in"))
      (node (ref "IC6") (pin "10") (pinfunction "VCC_10") (pintype "power_in"))
      (node (ref "IC7") (pin "4") (pinfunction "VCC_4") (pintype "power_in"))
      (node (ref "IC7") (pin "7") (pinfunction "A0_7") (pintype "input"))
      (node (ref "IC8") (pin "10") (pinfunction "VCC_10") (pintype "power_in"))
      (node (ref "IC8") (pin "8") (pinfunction "ADR0_8") (pintype "input"))
      (node (ref "Q1") (pin "4") (pinfunction "VCC_4") (pintype "power_in"))
      (node (ref "Q5") (pin "C") (pinfunction "C_C") (pintype "passive"))
      (node (ref "Q6") (pin "C") (pinfunction "C_C") (pintype "passive"))
      (node (ref "Q7") (pin "C") (pinfunction "C_C") (pintype "passive"))
      (node (ref "Q8") (pin "C") (pinfunction "C_C") (pintype "passive"))
      (node (ref "R1") (pin "1") (pinfunction "1_1") (pintype "passive"))
      (node (ref "R10") (pin "1") (pinfunction "1_1") (pintype "passive"))
      (node (ref "R2") (pin "1") (pinfunction "1_1") (pintype "passive"))
      (node (ref "R33") (pin "2") (pinfunction "2_2") (pintype "passive"))
      (node (ref "R34") (pin "2") (pinfunction "2_2") (pintype "passive"))
      (node (ref "R35") (pin "2") (pinfunction "2_2") (pintype "passive"))
      (node (ref "R4") (pin "1") (pinfunction "1_1") (pintype "passive"))
      (node (ref "R5") (pin "1") (pinfunction "1_1") (pintype "passive"))
      (node (ref "R7") (pin "2") (pinfunction "2_2") (pintype "passive"))
      (node (ref "R8") (pin "2") (pinfunction "2_2") (pintype "passive"))
    )
    (net (code "72") (name "unconnected-(CON_PROG-Pad6)") (class "Default")
      (node (ref "CON_PROG") (pin "6") (pinfunction "6_6") (pintype "bidirectional"))
    )
    (net (code "73") (name "unconnected-(IC2-SC1-Pad8)") (class "Default")
      (node (ref "IC2") (pin "8") (pinfunction "SC1_8") (pintype "bidirectional"))
    )
    (net (code "74") (name "unconnected-(IC2-SD1-Pad7)") (class "Default")
      (node (ref "IC2") (pin "7") (pinfunction "SD1_7") (pintype "bidirectional"))
    )
    (net (code "75") (name "unconnected-(IC5-FAULTN-Pad6)") (class "Default")
      (node (ref "IC5") (pin "6") (pinfunction "FAULTN_6") (pintype "output"))
    )
    (net (code "76") (name "unconnected-(IC7-FAULTN-Pad6)") (class "Default")
      (node (ref "IC7") (pin "6") (pinfunction "FAULTN_6") (pintype "output"))
    )
  )
)
